# reduced.net
KiCad netlist of a schematic drawn in EAGLE
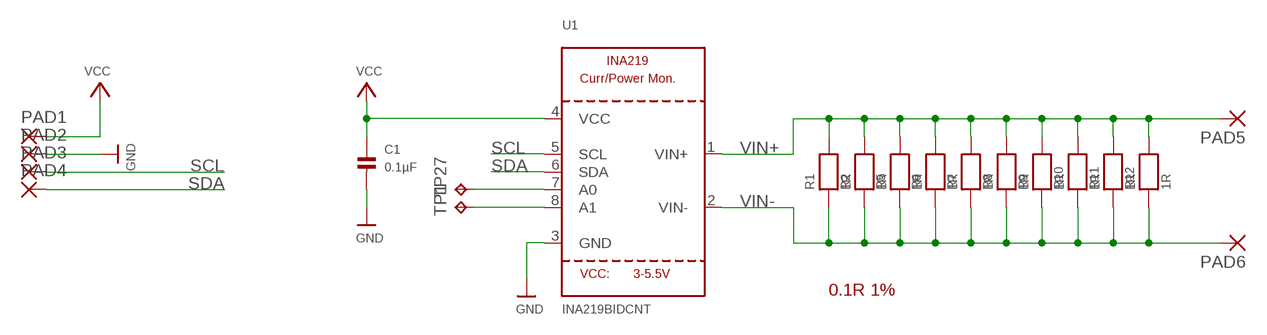
[diagram p0: schematic, sheet 1]

(export (version "E")
  (design (tool "Eeschema 10.0.6"))
  (components
    (comp (ref "C1")
      (value "0.1µF")
      (footprint "eagle-import:0603")
      (libsource (lib "eagle-import") (part "CAP_CERAMIC0603"))
    )
    (comp (ref "PAD1")
      (value "SMD2")
      (footprint "eagle-import:SMD1,27-2,54")
      (libsource (lib "eagle-import") (part "SMD2"))
    )
    (comp (ref "PAD2")
      (value "SMD2")
      (footprint "eagle-import:SMD1,27-2,54")
      (libsource (lib "eagle-import") (part "SMD2"))
    )
    (comp (ref "PAD3")
      (value "SMD2")
      (footprint "eagle-import:SMD1,27-2,54")
      (libsource (lib "eagle-import") (part "SMD2"))
    )
    (comp (ref "PAD4")
      (value "SMD2")
      (footprint "eagle-import:SMD1,27-2,54")
      (libsource (lib "eagle-import") (part "SMD2"))
    )
    (comp (ref "PAD5")
      (value "SMD2")
      (footprint "eagle-import:SMD1,27-2,54")
      (libsource (lib "eagle-import") (part "SMD2"))
    )
    (comp (ref "PAD6")
      (value "SMD2")
      (footprint "eagle-import:SMD1,27-2,54")
      (libsource (lib "eagle-import") (part "SMD2"))
    )
    (comp (ref "R1")
      (value "1R")
      (footprint "eagle-import:1206")
      (libsource (lib "eagle-import") (part "RESISTOR1206"))
    )
    (comp (ref "R2")
      (value "1R")
      (footprint "eagle-import:1206")
      (libsource (lib "eagle-import") (part "RESISTOR1206"))
    )
    (comp (ref "R5")
      (value "1R")
      (footprint "eagle-import:1206")
      (libsource (lib "eagle-import") (part "RESISTOR1206"))
    )
    (comp (ref "R6")
      (value "1R")
      (footprint "eagle-import:1206")
      (libsource (lib "eagle-import") (part "RESISTOR1206"))
    )
    (comp (ref "R7")
      (value "1R")
      (footprint "eagle-import:1206")
      (libsource (lib "eagle-import") (part "RESISTOR1206"))
    )
    (comp (ref "R8")
      (value "1R")
      (footprint "eagle-import:1206")
      (libsource (lib "eagle-import") (part "RESISTOR1206"))
    )
    (comp (ref "R9")
      (value "1R")
      (footprint "eagle-import:1206")
      (libsource (lib "eagle-import") (part "RESISTOR1206"))
    )
    (comp (ref "R10")
      (value "1R")
      (footprint "eagle-import:1206")
      (libsource (lib "eagle-import") (part "RESISTOR1206"))
    )
    (comp (ref "R11")
      (value "1R")
      (footprint "eagle-import:1206")
      (libsource (lib "eagle-import") (part "RESISTOR1206"))
    )
    (comp (ref "R12")
      (value "1R")
      (footprint "eagle-import:1206")
      (libsource (lib "eagle-import") (part "RESISTOR1206"))
    )
    (comp (ref "TP1")
      (value "TPTP06R")
      (footprint "eagle-import:TP06R")
      (libsource (lib "eagle-import") (part "TPTP06R"))
    )
    (comp (ref "TP27")
      (value "TPTP06R")
      (footprint "eagle-import:TP06R")
      (libsource (lib "eagle-import") (part "TPTP06R"))
    )
    (comp (ref "U1")
      (value "INA219BIDCNT")
      (footprint "eagle-import:SOT23-8")
      (libsource (lib "eagle-import") (part "INA219"))
    )
  )
  (nets
    (net (code "1") (name "/SCL") (class "Default")
      (node (ref "PAD3") (pin "1") (pinfunction "P_1") (pintype "passive"))
      (node (ref "U1") (pin "5") (pinfunction "SCL_5") (pintype "bidirectional"))
    )
    (net (code "2") (name "/SDA") (class "Default")
      (node (ref "PAD4") (pin "1") (pinfunction "P_1") (pintype "passive"))
      (node (ref "U1") (pin "6") (pinfunction "SDA_6") (pintype "bidirectional"))
    )
    (net (code "3") (name "/VIN+") (class "Default")
      (node (ref "PAD5") (pin "1") (pinfunction "P_1") (pintype "passive"))
      (node (ref "R1") (pin "2") (pinfunction "2_2") (pintype "passive"))
      (node (ref "R10") (pin "2") (pinfunction "2_2") (pintype "passive"))
      (node (ref "R11") (pin "2") (pinfunction "2_2") (pintype "passive"))
      (node (ref "R12") (pin "2") (pinfunction "2_2") (pintype "passive"))
      (node (ref "R2") (pin "2") (pinfunction "2_2") (pintype "passive"))
      (node (ref "R5") (pin "2") (pinfunction "2_2") (pintype "passive"))
      (node (ref "R6") (pin "2") (pinfunction "2_2") (pintype "passive"))
      (node (ref "R7") (pin "2") (pinfunction "2_2") (pintype "passive"))
      (node (ref "R8") (pin "2") (pinfunction "2_2") (pintype "passive"))
      (node (ref "R9") (pin "2") (pinfunction "2_2") (pintype "passive"))
      (node (ref "U1") (pin "1") (pinfunction "VIN+_1") (pintype "bidirectional"))
    )
    (net (code "4") (name "/VIN-") (class "Default")
      (node (ref "PAD6") (pin "1") (pinfunction "P_1") (pintype "passive"))
      (node (ref "R1") (pin "1") (pinfunction "1_1") (pintype "passive"))
      (node (ref "R10") (pin "1") (pinfunction "1_1") (pintype "passive"))
      (node (ref "R11") (pin "1") (pinfunction "1_1") (pintype "passive"))
      (node (ref "R12") (pin "1") (pinfunction "1_1") (pintype "passive"))
      (node (ref "R2") (pin "1") (pinfunction "1_1") (pintype "passive"))
      (node (ref "R5") (pin "1") (pinfunction "1_1") (pintype "passive"))
      (node (ref "R6") (pin "1") (pinfunction "1_1") (pintype "passive"))
      (node (ref "R7") (pin "1") (pinfunction "1_1") (pintype "passive"))
      (node (ref "R8") (pin "1") (pinfunction "1_1") (pintype "passive"))
      (node (ref "R9") (pin "1") (pinfunction "1_1") (pintype "passive"))
      (node (ref "U1") (pin "2") (pinfunction "VIN-_2") (pintype "bidirectional"))
    )
    (net (code "5") (name "GND") (class "Default")
      (node (ref "C1") (pin "2") (pinfunction "P$2_2") (pintype "passive"))
      (node (ref "PAD2") (pin "1") (pinfunction "P_1") (pintype "passive"))
      (node (ref "U1") (pin "3") (pinfunction "GND_3") (pintype "bidirectional"))
    )
    (net (code "6") (name "Net-(U1-A0)") (class "Default")
      (node (ref "TP27") (pin "TP") (pinfunction "TP_TP") (pintype "input"))
      (node (ref "U1") (pin "7") (pinfunction "A0_7") (pintype "bidirectional"))
    )
    (net (code "7") (name "Net-(U1-A1)") (class "Default")
      (node (ref "TP1") (pin "TP") (pinfunction "TP_TP") (pintype "input"))
      (node (ref "U1") (pin "8") (pinfunction "A1_8") (pintype "bidirectional"))
    )
    (net (code "8") (name "VCC") (class "Default")
      (node (ref "C1") (pin "1") (pinfunction "P$1_1") (pintype "passive"))
      (node (ref "PAD1") (pin "1") (pinfunction "P_1") (pintype "passive"))
      (node (ref "U1") (pin "4") (pinfunction "VCC_4") (pintype "bidirectional"))
    )
  )
)
